# STM32F030_-_VGA_minimal_v4.net
KiCad netlist of a schematic drawn in EAGLE
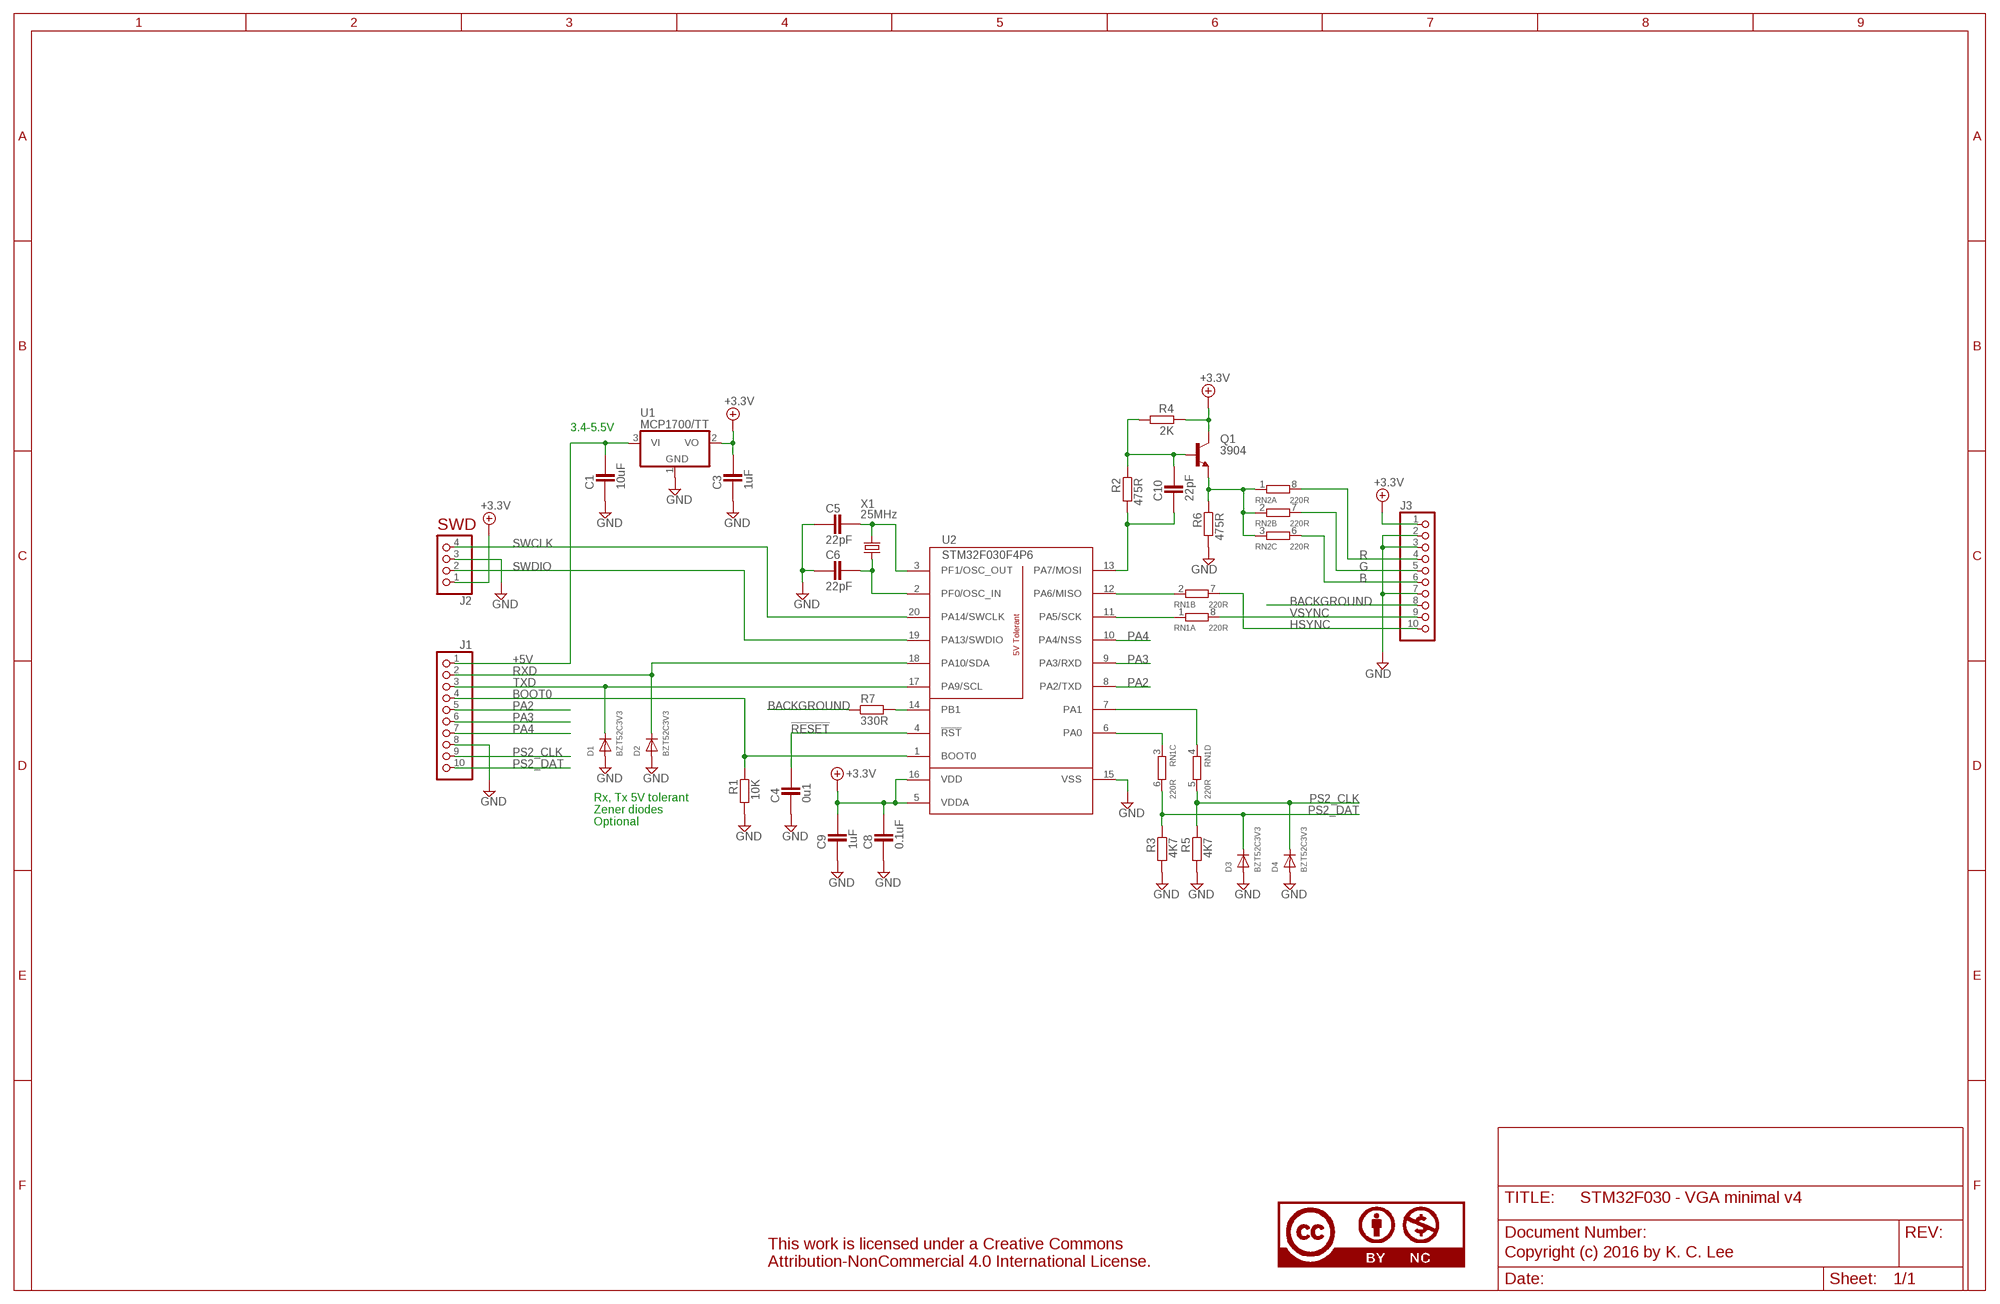
[diagram p0: schematic, sheet 1]

(export (version "E")
  (design (tool "Eeschema 10.0.6"))
  (components
    (comp (ref "C1")
      (value "10uF")
      (footprint "eagle-import:CAPC2012X145AN")
      (fields (field (name "PARTNO") "0U1, 0603"))
      (libsource (lib "eagle-import") (part "CAPACITOR_0805"))
    )
    (comp (ref "C3")
      (value "1uF")
      (footprint "eagle-import:CAPC2012X145AN")
      (fields (field (name "PARTNO") "0U1, 0603"))
      (libsource (lib "eagle-import") (part "CAPACITOR_0805"))
    )
    (comp (ref "C4")
      (value "0u1")
      (footprint "eagle-import:CAPC1608X92N")
      (fields (field (name "PARTNO") "0U1, 0603"))
      (libsource (lib "eagle-import") (part "CAPACITOR_0603"))
    )
    (comp (ref "C5")
      (value "22pF")
      (footprint "eagle-import:CAPC1608X92N")
      (fields (field (name "PARTNO") "0U1, 0603"))
      (libsource (lib "eagle-import") (part "CAPACITOR_0603"))
    )
    (comp (ref "C6")
      (value "22pF")
      (footprint "eagle-import:CAPC1608X92N")
      (fields (field (name "PARTNO") "0U1, 0603"))
      (libsource (lib "eagle-import") (part "CAPACITOR_0603"))
    )
    (comp (ref "C8")
      (value "0.1uF")
      (footprint "eagle-import:CAPC1608X92N")
      (fields (field (name "PARTNO") "1UF, 0603"))
      (libsource (lib "eagle-import") (part "CAPACITOR_0603"))
    )
    (comp (ref "C9")
      (value "1uF")
      (footprint "eagle-import:CAPC1608X92N")
      (fields (field (name "PARTNO") "0U1, 0603"))
      (libsource (lib "eagle-import") (part "CAPACITOR_0603"))
    )
    (comp (ref "C10")
      (value "22pF")
      (footprint "eagle-import:CAPC1608X92N")
      (fields (field (name "PARTNO") "0U1, 0603"))
      (libsource (lib "eagle-import") (part "CAPACITOR_0603"))
    )
    (comp (ref "D1")
      (value "BZT52C3V3")
      (footprint "eagle-import:SOD-123")
      (libsource (lib "eagle-import") (part "DIODESOD-123"))
    )
    (comp (ref "D2")
      (value "BZT52C3V3")
      (footprint "eagle-import:SOD-123")
      (libsource (lib "eagle-import") (part "DIODESOD-123"))
    )
    (comp (ref "D3")
      (value "BZT52C3V3")
      (footprint "eagle-import:SOD-123")
      (libsource (lib "eagle-import") (part "DIODESOD-123"))
    )
    (comp (ref "D4")
      (value "BZT52C3V3")
      (footprint "eagle-import:SOD-123")
      (libsource (lib "eagle-import") (part "DIODESOD-123"))
    )
    (comp (ref "J1")
      (value "PINHD-1X10")
      (footprint "eagle-import:1X10")
      (libsource (lib "eagle-import") (part "PINHD-1X10"))
    )
    (comp (ref "J2")
      (value "PINHD-1X4_2.54")
      (footprint "eagle-import:1X04")
      (libsource (lib "eagle-import") (part "PINHD-1X4_2.54"))
    )
    (comp (ref "J3")
      (value "PINHD-1X10")
      (footprint "eagle-import:1X10")
      (libsource (lib "eagle-import") (part "PINHD-1X10"))
    )
    (comp (ref "Q1")
      (value "3904")
      (footprint "eagle-import:SOT95P280X135-3N")
      (libsource (lib "eagle-import") (part "NPN_SOT-23"))
    )
    (comp (ref "R1")
      (value "10K")
      (footprint "eagle-import:RESC1608X55N")
      (fields (field (name "PARTNO") "10K, 0603"))
      (libsource (lib "eagle-import") (part "RESISTOR_0603"))
    )
    (comp (ref "R2")
      (value "475R")
      (footprint "eagle-import:RESC1608X55N")
      (fields (field (name "PARTNO") "10K, 0603"))
      (libsource (lib "eagle-import") (part "RESISTOR_0603"))
    )
    (comp (ref "R3")
      (value "4K7")
      (footprint "eagle-import:RESC1608X55N")
      (fields (field (name "PARTNO") "10K, 0603"))
      (libsource (lib "eagle-import") (part "RESISTOR_0603"))
    )
    (comp (ref "R4")
      (value "2K")
      (footprint "eagle-import:RESC1608X55N")
      (fields (field (name "PARTNO") "10K, 0603"))
      (libsource (lib "eagle-import") (part "RESISTOR_0603"))
    )
    (comp (ref "R5")
      (value "4K7")
      (footprint "eagle-import:RESC1608X55N")
      (fields (field (name "PARTNO") "10K, 0603"))
      (libsource (lib "eagle-import") (part "RESISTOR_0603"))
    )
    (comp (ref "R6")
      (value "475R")
      (footprint "eagle-import:RESC1608X55N")
      (fields (field (name "PARTNO") "10K, 0603"))
      (libsource (lib "eagle-import") (part "RESISTOR_0603"))
    )
    (comp (ref "R7")
      (value "330R")
      (footprint "eagle-import:RESC1608X55N")
      (fields (field (name "PARTNO") "10K, 0603"))
      (libsource (lib "eagle-import") (part "RESISTOR_0603"))
    )
    (comp (ref "RN1")
      (value "220R")
      (footprint "eagle-import:CAT16")
      (libsource (lib "eagle-import") (part "4R-NCAT16"))
    )
    (comp (ref "RN2")
      (value "220R")
      (footprint "eagle-import:CAT16")
      (libsource (lib "eagle-import") (part "4R-NCAT16"))
    )
    (comp (ref "U$1")
      (value "CC-BY-NC75%")
      (footprint "eagle-import:CC-BY-NC-75")
      (libsource (lib "eagle-import") (part "CC-BY-NC75%"))
    )
    (comp (ref "U1")
      (value "MCP1700/TT")
      (footprint "eagle-import:SOT95P280X135-3N")
      (libsource (lib "eagle-import") (part "MCP1700/TT"))
    )
    (comp (ref "U2")
      (value "STM32F030F4P6")
      (footprint "eagle-import:TSSOP20")
      (libsource (lib "eagle-import") (part "STM32F030F4P6"))
    )
    (comp (ref "X1")
      (value "25MHz")
      (footprint "eagle-import:SM49")
      (libsource (lib "eagle-import") (part "CRYSTALSM49"))
    )
  )
  (nets
    (net (code "1") (name "+3.3V") (class "Default")
      (node (ref "C3") (pin "2") (pinfunction "2_2") (pintype "passive"))
      (node (ref "C8") (pin "2") (pinfunction "2_2") (pintype "passive"))
      (node (ref "C9") (pin "2") (pinfunction "2_2") (pintype "passive"))
      (node (ref "J2") (pin "1") (pinfunction "1_1") (pintype "passive"))
      (node (ref "J3") (pin "1") (pinfunction "1_1") (pintype "passive"))
      (node (ref "Q1") (pin "3") (pinfunction "C_3") (pintype "passive"))
      (node (ref "R4") (pin "1") (pinfunction "1_1") (pintype "passive"))
      (node (ref "U1") (pin "2") (pinfunction "VO_2") (pintype "passive"))
      (node (ref "U2") (pin "16") (pinfunction "VDD_16") (pintype "input"))
      (node (ref "U2") (pin "5") (pinfunction "VDDA_5") (pintype "input"))
    )
    (net (code "2") (name "/+5V") (class "Default")
      (node (ref "C1") (pin "2") (pinfunction "2_2") (pintype "passive"))
      (node (ref "J1") (pin "1") (pinfunction "1_1") (pintype "passive"))
      (node (ref "U1") (pin "3") (pinfunction "VI_3") (pintype "input"))
    )
    (net (code "3") (name "/B") (class "Default")
      (node (ref "J3") (pin "6") (pinfunction "6_6") (pintype "passive"))
      (node (ref "RN2") (pin "6") (pinfunction "2_6") (pintype "passive"))
    )
    (net (code "4") (name "/BACKGROUND") (class "Default")
      (node (ref "J3") (pin "8") (pinfunction "8_8") (pintype "passive"))
      (node (ref "R7") (pin "1") (pinfunction "1_1") (pintype "passive"))
    )
    (net (code "5") (name "/BOOT0") (class "Default")
      (node (ref "J1") (pin "4") (pinfunction "4_4") (pintype "passive"))
      (node (ref "R1") (pin "1") (pinfunction "1_1") (pintype "passive"))
      (node (ref "U2") (pin "1") (pinfunction "BOOT0_1") (pintype "input"))
    )
    (net (code "6") (name "/G") (class "Default")
      (node (ref "J3") (pin "5") (pinfunction "5_5") (pintype "passive"))
      (node (ref "RN2") (pin "7") (pinfunction "2_7") (pintype "passive"))
    )
    (net (code "7") (name "/HSYNC") (class "Default")
      (node (ref "J3") (pin "10") (pinfunction "10_10") (pintype "passive"))
      (node (ref "RN1") (pin "7") (pinfunction "2_7") (pintype "passive"))
    )
    (net (code "8") (name "/PA2") (class "Default")
      (node (ref "J1") (pin "5") (pinfunction "5_5") (pintype "passive"))
      (node (ref "U2") (pin "8") (pinfunction "PA2/TXD_8") (pintype "bidirectional"))
    )
    (net (code "9") (name "/PA3") (class "Default")
      (node (ref "J1") (pin "6") (pinfunction "6_6") (pintype "passive"))
      (node (ref "U2") (pin "9") (pinfunction "PA3/RXD_9") (pintype "bidirectional"))
    )
    (net (code "10") (name "/PA4") (class "Default")
      (node (ref "J1") (pin "7") (pinfunction "7_7") (pintype "passive"))
      (node (ref "U2") (pin "10") (pinfunction "PA4/NSS_10") (pintype "bidirectional"))
    )
    (net (code "11") (name "/PS2_CLK") (class "Default")
      (node (ref "D4") (pin "C") (pinfunction "C_C") (pintype "passive"))
      (node (ref "J1") (pin "9") (pinfunction "9_9") (pintype "passive"))
      (node (ref "R5") (pin "1") (pinfunction "1_1") (pintype "passive"))
      (node (ref "RN1") (pin "5") (pinfunction "2_5") (pintype "passive"))
    )
    (net (code "12") (name "/PS2_DAT") (class "Default")
      (node (ref "D3") (pin "C") (pinfunction "C_C") (pintype "passive"))
      (node (ref "J1") (pin "10") (pinfunction "10_10") (pintype "passive"))
      (node (ref "R3") (pin "1") (pinfunction "1_1") (pintype "passive"))
      (node (ref "RN1") (pin "6") (pinfunction "2_6") (pintype "passive"))
    )
    (net (code "13") (name "/R") (class "Default")
      (node (ref "J3") (pin "4") (pinfunction "4_4") (pintype "passive"))
      (node (ref "RN2") (pin "8") (pinfunction "2_8") (pintype "passive"))
    )
    (net (code "14") (name "/RXD") (class "Default")
      (node (ref "D2") (pin "C") (pinfunction "C_C") (pintype "passive"))
      (node (ref "J1") (pin "2") (pinfunction "2_2") (pintype "passive"))
      (node (ref "U2") (pin "18") (pinfunction "PA10/SDA_18") (pintype "bidirectional"))
    )
    (net (code "15") (name "/SWCLK") (class "Default")
      (node (ref "J2") (pin "4") (pinfunction "4_4") (pintype "passive"))
      (node (ref "U2") (pin "20") (pinfunction "PA14/SWCLK_20") (pintype "bidirectional"))
    )
    (net (code "16") (name "/SWDIO") (class "Default")
      (node (ref "J2") (pin "2") (pinfunction "2_2") (pintype "passive"))
      (node (ref "U2") (pin "19") (pinfunction "PA13/SWDIO_19") (pintype "bidirectional"))
    )
    (net (code "17") (name "/TXD") (class "Default")
      (node (ref "D1") (pin "C") (pinfunction "C_C") (pintype "passive"))
      (node (ref "J1") (pin "3") (pinfunction "3_3") (pintype "passive"))
      (node (ref "U2") (pin "17") (pinfunction "PA9/SCL_17") (pintype "bidirectional"))
    )
    (net (code "18") (name "/VSYNC") (class "Default")
      (node (ref "J3") (pin "9") (pinfunction "9_9") (pintype "passive"))
      (node (ref "RN1") (pin "8") (pinfunction "2_8") (pintype "passive"))
    )
    (net (code "19") (name "/~{RESET}") (class "Default")
      (node (ref "C4") (pin "2") (pinfunction "2_2") (pintype "passive"))
      (node (ref "U2") (pin "4") (pinfunction "~{RST}_4") (pintype "input"))
    )
    (net (code "20") (name "GND") (class "Default")
      (node (ref "C1") (pin "1") (pinfunction "1_1") (pintype "passive"))
      (node (ref "C3") (pin "1") (pinfunction "1_1") (pintype "passive"))
      (node (ref "C4") (pin "1") (pinfunction "1_1") (pintype "passive"))
      (node (ref "C5") (pin "1") (pinfunction "1_1") (pintype "passive"))
      (node (ref "C6") (pin "1") (pinfunction "1_1") (pintype "passive"))
      (node (ref "C8") (pin "1") (pinfunction "1_1") (pintype "passive"))
      (node (ref "C9") (pin "1") (pinfunction "1_1") (pintype "passive"))
      (node (ref "D1") (pin "A") (pinfunction "A_A") (pintype "passive"))
      (node (ref "D2") (pin "A") (pinfunction "A_A") (pintype "passive"))
      (node (ref "D3") (pin "A") (pinfunction "A_A") (pintype "passive"))
      (node (ref "D4") (pin "A") (pinfunction "A_A") (pintype "passive"))
      (node (ref "J1") (pin "8") (pinfunction "8_8") (pintype "passive"))
      (node (ref "J2") (pin "3") (pinfunction "3_3") (pintype "passive"))
      (node (ref "J3") (pin "2") (pinfunction "2_2") (pintype "passive"))
      (node (ref "J3") (pin "3") (pinfunction "3_3") (pintype "passive"))
      (node (ref "J3") (pin "7") (pinfunction "7_7") (pintype "passive"))
      (node (ref "R1") (pin "2") (pinfunction "2_2") (pintype "passive"))
      (node (ref "R3") (pin "2") (pinfunction "2_2") (pintype "passive"))
      (node (ref "R5") (pin "2") (pinfunction "2_2") (pintype "passive"))
      (node (ref "R6") (pin "2") (pinfunction "2_2") (pintype "passive"))
      (node (ref "U1") (pin "1") (pinfunction "GND_1") (pintype "passive"))
      (node (ref "U2") (pin "15") (pinfunction "VSS_15") (pintype "input"))
    )
    (net (code "21") (name "Net-(Q1-B)") (class "Default")
      (node (ref "C10") (pin "2") (pinfunction "2_2") (pintype "passive"))
      (node (ref "Q1") (pin "1") (pinfunction "B_1") (pintype "passive"))
      (node (ref "R2") (pin "1") (pinfunction "1_1") (pintype "passive"))
      (node (ref "R4") (pin "2") (pinfunction "2_2") (pintype "passive"))
    )
    (net (code "22") (name "Net-(Q1-E)") (class "Default")
      (node (ref "Q1") (pin "2") (pinfunction "E_2") (pintype "passive"))
      (node (ref "R6") (pin "1") (pinfunction "1_1") (pintype "passive"))
      (node (ref "RN2") (pin "1") (pinfunction "1_1") (pintype "passive"))
      (node (ref "RN2") (pin "2") (pinfunction "1_2") (pintype "passive"))
      (node (ref "RN2") (pin "3") (pinfunction "1_3") (pintype "passive"))
    )
    (net (code "23") (name "Net-(RN1B-1)") (class "Default")
      (node (ref "RN1") (pin "2") (pinfunction "1_2") (pintype "passive"))
      (node (ref "U2") (pin "12") (pinfunction "PA6/MISO_12") (pintype "bidirectional"))
    )
    (net (code "24") (name "Net-(RN1C-1)") (class "Default")
      (node (ref "RN1") (pin "3") (pinfunction "1_3") (pintype "passive"))
      (node (ref "U2") (pin "6") (pinfunction "PA0_6") (pintype "bidirectional"))
    )
    (net (code "25") (name "Net-(RN1D-1)") (class "Default")
      (node (ref "RN1") (pin "4") (pinfunction "1_4") (pintype "passive"))
      (node (ref "U2") (pin "7") (pinfunction "PA1_7") (pintype "bidirectional"))
    )
    (net (code "26") (name "Net-(U2-PA5{slash}SCK)") (class "Default")
      (node (ref "RN1") (pin "1") (pinfunction "1_1") (pintype "passive"))
      (node (ref "U2") (pin "11") (pinfunction "PA5/SCK_11") (pintype "bidirectional"))
    )
    (net (code "27") (name "Net-(U2-PA7{slash}MOSI)") (class "Default")
      (node (ref "C10") (pin "1") (pinfunction "1_1") (pintype "passive"))
      (node (ref "R2") (pin "2") (pinfunction "2_2") (pintype "passive"))
      (node (ref "U2") (pin "13") (pinfunction "PA7/MOSI_13") (pintype "bidirectional"))
    )
    (net (code "28") (name "Net-(U2-PB1)") (class "Default")
      (node (ref "R7") (pin "2") (pinfunction "2_2") (pintype "passive"))
      (node (ref "U2") (pin "14") (pinfunction "PB1_14") (pintype "bidirectional"))
    )
    (net (code "29") (name "Net-(U2-PF0{slash}OSC_IN)") (class "Default")
      (node (ref "C6") (pin "2") (pinfunction "2_2") (pintype "passive"))
      (node (ref "U2") (pin "2") (pinfunction "PF0/OSC_IN_2") (pintype "input"))
      (node (ref "X1") (pin "1") (pinfunction "1_1") (pintype "passive"))
    )
    (net (code "30") (name "Net-(U2-PF1{slash}OSC_OUT)") (class "Default")
      (node (ref "C5") (pin "2") (pinfunction "2_2") (pintype "passive"))
      (node (ref "U2") (pin "3") (pinfunction "PF1/OSC_OUT_3") (pintype "output"))
      (node (ref "X1") (pin "2") (pinfunction "2_2") (pintype "passive"))
    )
  )
)
